# MASTER_CEAQL_PCB.net
KiCad netlist of a schematic drawn in EAGLE
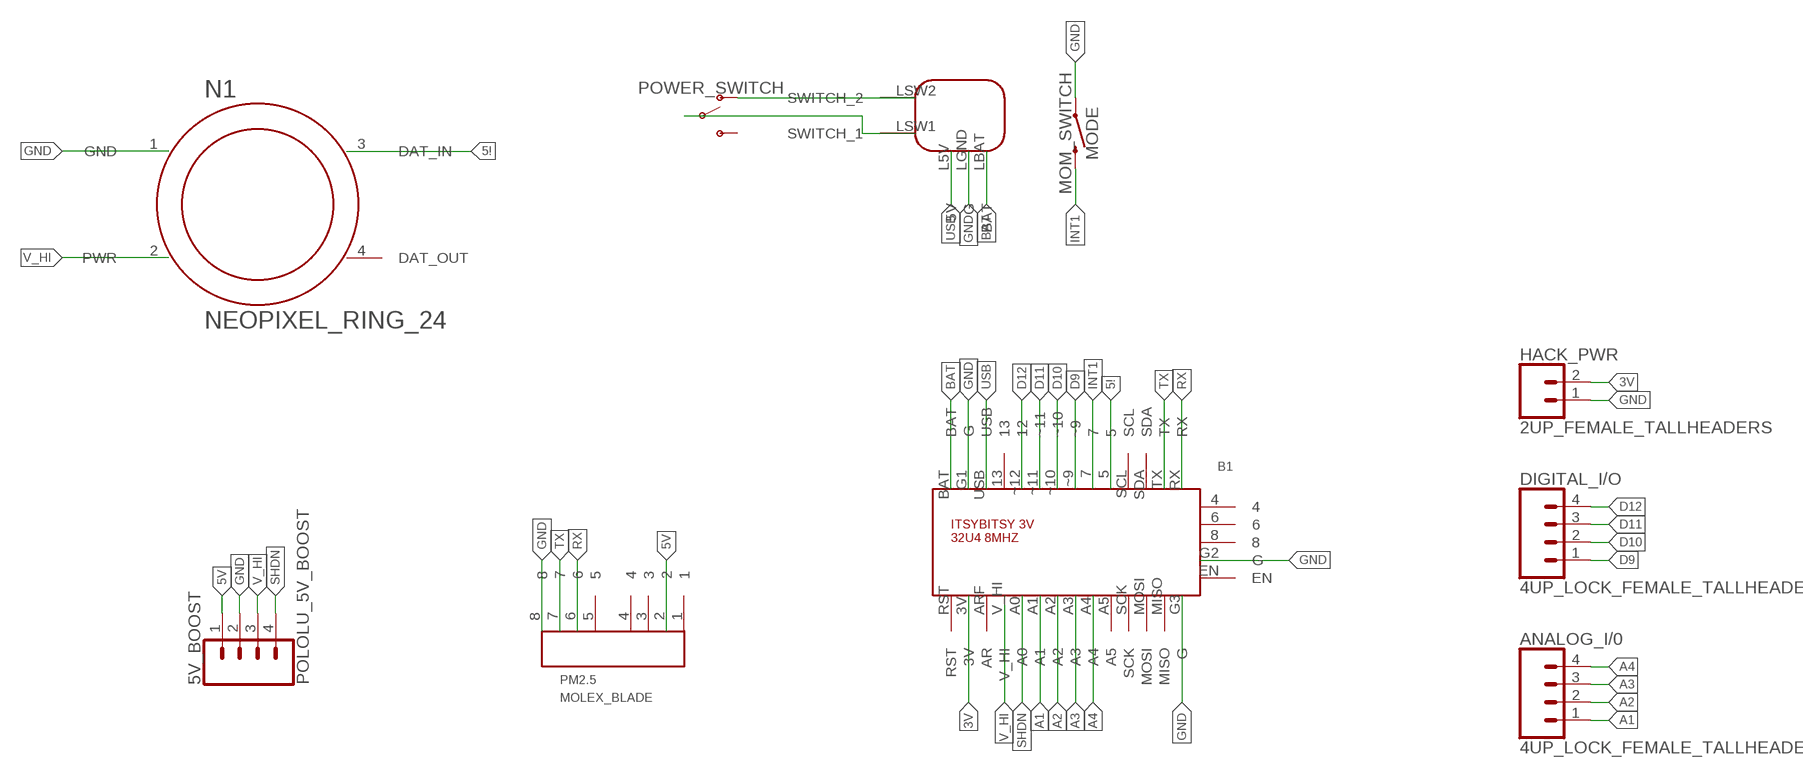
[diagram p0: schematic, sheet 1]

(export (version "E")
  (design (tool "Eeschema 10.0.6"))
  (components
    (comp (ref "5V_BOOST")
      (value "POLOLU_5V_BOOST")
      (footprint "eagle-import:POLOLU_5V_HEADERS")
      (libsource (lib "eagle-import") (part "POLOLU_5V_BOOST"))
    )
    (comp (ref "ANALOG_I/0")
      (value "4UP_LOCK_FEMALE_TALLHEADERS")
      (footprint "eagle-import:1X04_LOCK_TALL")
      (libsource (lib "eagle-import") (part "4UP_LOCK_FEMALE_TALLHEADERS"))
    )
    (comp (ref "B1")
      (value "ITSY_BITSY")
      (footprint "eagle-import:ITSY_BITSY")
      (libsource (lib "eagle-import") (part "ITSY_BITSY"))
    )
    (comp (ref "DIGITAL_I/O")
      (value "4UP_LOCK_FEMALE_TALLHEADERS")
      (footprint "eagle-import:1X04_LOCK_TALL")
      (libsource (lib "eagle-import") (part "4UP_LOCK_FEMALE_TALLHEADERS"))
    )
    (comp (ref "HACK_PWR")
      (value "2UP_FEMALE_TALLHEADERS")
      (footprint "eagle-import:1X02")
      (libsource (lib "eagle-import") (part "2UP_FEMALE_TALLHEADERS"))
    )
    (comp (ref "L1")
      (value "LIPOLY_CHARGER")
      (footprint "eagle-import:LIPOLY_CHARGER")
      (libsource (lib "eagle-import") (part "LIPOLY_CHARGER"))
    )
    (comp (ref "MODE")
      (value "MOM_SWITCH")
      (footprint "eagle-import:TACTILE_SWITCH_PTH_6.0MM")
      (libsource (lib "eagle-import") (part "MOM_SWITCH_B3F-1000"))
    )
    (comp (ref "N1")
      (value "NEOPIXEL_RING_24")
      (footprint "eagle-import:NEOPIXEL_RNG_24")
      (libsource (lib "eagle-import") (part "NEOPIXEL_RING_24"))
    )
    (comp (ref "PM2.5")
      (value "MOLEX_BLADE")
      (footprint "eagle-import:53047-08")
      (libsource (lib "eagle-import") (part "MOLEX_BLADE"))
    )
    (comp (ref "POWER_SWITCH")
      (value "SWITCH_SPDT_PINMOUNT")
      (footprint "eagle-import:SWITCH_SPDT_PTH_11.6X4.0MM_LOCK")
      (libsource (lib "eagle-import") (part "SWITCH_SPDT_PINMOUNT"))
    )
  )
  (nets
    (net (code "1") (name "/5~{}") (class "Default")
      (node (ref "B1") (pin "5") (pinfunction "5_5") (pintype "output"))
      (node (ref "N1") (pin "3") (pinfunction "DAT_IN_3") (pintype "bidirectional"))
    )
    (net (code "2") (name "3V") (class "Default")
      (node (ref "B1") (pin "3V") (pinfunction "3V_3V") (pintype "power_in"))
      (node (ref "HACK_PWR") (pin "2") (pinfunction "2_2") (pintype "passive"))
    )
    (net (code "3") (name "5V") (class "Default")
      (node (ref "5V_BOOST") (pin "1") (pinfunction "1_1") (pintype "passive"))
      (node (ref "PM2.5") (pin "2") (pinfunction "2_2") (pintype "bidirectional"))
    )
    (net (code "4") (name "A1") (class "Default")
      (node (ref "ANALOG_I/0") (pin "1") (pinfunction "1_1") (pintype "passive"))
      (node (ref "B1") (pin "A1") (pinfunction "A1_A1") (pintype "bidirectional"))
    )
    (net (code "5") (name "A2") (class "Default")
      (node (ref "ANALOG_I/0") (pin "2") (pinfunction "2_2") (pintype "passive"))
      (node (ref "B1") (pin "A2") (pinfunction "A2_A2") (pintype "bidirectional"))
    )
    (net (code "6") (name "A3") (class "Default")
      (node (ref "ANALOG_I/0") (pin "3") (pinfunction "3_3") (pintype "passive"))
      (node (ref "B1") (pin "A3") (pinfunction "A3_A3") (pintype "bidirectional"))
    )
    (net (code "7") (name "A4") (class "Default")
      (node (ref "ANALOG_I/0") (pin "4") (pinfunction "4_4") (pintype "passive"))
      (node (ref "B1") (pin "A4") (pinfunction "A4_A4") (pintype "bidirectional"))
    )
    (net (code "8") (name "BAT") (class "Default")
      (node (ref "B1") (pin "BAT") (pinfunction "BAT_BAT") (pintype "power_in"))
      (node (ref "L1") (pin "LBAT") (pinfunction "BAT_LBAT") (pintype "bidirectional"))
    )
    (net (code "9") (name "D9") (class "Default")
      (node (ref "B1") (pin "~9") (pinfunction "~{9}_~9") (pintype "bidirectional"))
      (node (ref "DIGITAL_I/O") (pin "1") (pinfunction "1_1") (pintype "passive"))
    )
    (net (code "10") (name "D10") (class "Default")
      (node (ref "B1") (pin "~10") (pinfunction "~{10}_~10") (pintype "bidirectional"))
      (node (ref "DIGITAL_I/O") (pin "2") (pinfunction "2_2") (pintype "passive"))
    )
    (net (code "11") (name "D11") (class "Default")
      (node (ref "B1") (pin "~11") (pinfunction "~{11}_~11") (pintype "bidirectional"))
      (node (ref "DIGITAL_I/O") (pin "3") (pinfunction "3_3") (pintype "passive"))
    )
    (net (code "12") (name "D12") (class "Default")
      (node (ref "B1") (pin "~12") (pinfunction "12_~12") (pintype "bidirectional"))
      (node (ref "DIGITAL_I/O") (pin "4") (pinfunction "4_4") (pintype "passive"))
    )
    (net (code "13") (name "GND") (class "Default")
      (node (ref "5V_BOOST") (pin "2") (pinfunction "2_2") (pintype "passive"))
      (node (ref "B1") (pin "G1") (pinfunction "G_G1") (pintype "power_in"))
      (node (ref "B1") (pin "G2") (pinfunction "G_G2") (pintype "power_in"))
      (node (ref "B1") (pin "G3") (pinfunction "G_G3") (pintype "power_in"))
      (node (ref "HACK_PWR") (pin "1") (pinfunction "1_1") (pintype "passive"))
      (node (ref "L1") (pin "LGND") (pinfunction "G_LGND") (pintype "bidirectional"))
      (node (ref "MODE") (pin "1") (pinfunction "1_1") (pintype "passive"))
      (node (ref "N1") (pin "1") (pinfunction "GND_1") (pintype "bidirectional"))
      (node (ref "PM2.5") (pin "8") (pinfunction "8_8") (pintype "bidirectional"))
    )
    (net (code "14") (name "INT1") (class "Default")
      (node (ref "B1") (pin "7") (pinfunction "7_7") (pintype "bidirectional"))
      (node (ref "MODE") (pin "2") (pinfunction "2_2") (pintype "passive"))
    )
    (net (code "15") (name "Net-(L1-SWITCH_1)") (class "Default")
      (node (ref "L1") (pin "LSW1") (pinfunction "SWITCH_1_LSW1") (pintype "bidirectional"))
      (node (ref "POWER_SWITCH") (pin "2") (pinfunction "P_2") (pintype "passive"))
    )
    (net (code "16") (name "Net-(L1-SWITCH_2)") (class "Default")
      (node (ref "L1") (pin "LSW2") (pinfunction "SWITCH_2_LSW2") (pintype "bidirectional"))
      (node (ref "POWER_SWITCH") (pin "1") (pinfunction "O_1") (pintype "passive"))
    )
    (net (code "17") (name "RX") (class "Default")
      (node (ref "B1") (pin "RX") (pinfunction "RX_RX") (pintype "bidirectional"))
      (node (ref "PM2.5") (pin "6") (pinfunction "6_6") (pintype "bidirectional"))
    )
    (net (code "18") (name "SHDN") (class "Default")
      (node (ref "5V_BOOST") (pin "4") (pinfunction "4_4") (pintype "passive"))
      (node (ref "B1") (pin "A0") (pinfunction "A0_A0") (pintype "bidirectional"))
    )
    (net (code "19") (name "TX") (class "Default")
      (node (ref "B1") (pin "TX") (pinfunction "TX_TX") (pintype "bidirectional"))
      (node (ref "PM2.5") (pin "7") (pinfunction "7_7") (pintype "bidirectional"))
    )
    (net (code "20") (name "USB") (class "Default")
      (node (ref "B1") (pin "USB") (pinfunction "USB_USB") (pintype "power_in"))
      (node (ref "L1") (pin "L5V") (pinfunction "5V_L5V") (pintype "bidirectional"))
    )
    (net (code "21") (name "V_HI") (class "Default")
      (node (ref "5V_BOOST") (pin "3") (pinfunction "3_3") (pintype "passive"))
      (node (ref "B1") (pin "V_HI") (pinfunction "V_HI_V_HI") (pintype "power_in"))
      (node (ref "N1") (pin "2") (pinfunction "PWR_2") (pintype "bidirectional"))
    )
    (net (code "22") (name "unconnected-(B1-AR-PadARF)") (class "Default")
      (node (ref "B1") (pin "ARF") (pinfunction "AR_ARF") (pintype "bidirectional"))
    )
    (net (code "23") (name "unconnected-(B1-Pad4)") (class "Default")
      (node (ref "B1") (pin "4") (pinfunction "4_4") (pintype "bidirectional"))
    )
    (net (code "24") (name "unconnected-(B1-Pad6)") (class "Default")
      (node (ref "B1") (pin "6") (pinfunction "6_6") (pintype "bidirectional"))
    )
    (net (code "25") (name "unconnected-(B1-Pad8)") (class "Default")
      (node (ref "B1") (pin "8") (pinfunction "8_8") (pintype "bidirectional"))
    )
    (net (code "26") (name "unconnected-(B1-Pad13)") (class "Default")
      (node (ref "B1") (pin "13") (pinfunction "13_13") (pintype "bidirectional"))
    )
    (net (code "27") (name "unconnected-(B1-PadA5)") (class "Default")
      (node (ref "B1") (pin "A5") (pinfunction "A5_A5") (pintype "bidirectional"))
    )
    (net (code "28") (name "unconnected-(B1-PadEN)") (class "Default")
      (node (ref "B1") (pin "EN") (pinfunction "EN_EN") (pintype "bidirectional"))
    )
    (net (code "29") (name "unconnected-(B1-PadMISO)") (class "Default")
      (node (ref "B1") (pin "MISO") (pinfunction "MISO_MISO") (pintype "bidirectional"))
    )
    (net (code "30") (name "unconnected-(B1-PadMOSI)") (class "Default")
      (node (ref "B1") (pin "MOSI") (pinfunction "MOSI_MOSI") (pintype "bidirectional"))
    )
    (net (code "31") (name "unconnected-(B1-PadRST)") (class "Default")
      (node (ref "B1") (pin "RST") (pinfunction "RST_RST") (pintype "bidirectional"))
    )
    (net (code "32") (name "unconnected-(B1-PadSCK)") (class "Default")
      (node (ref "B1") (pin "SCK") (pinfunction "SCK_SCK") (pintype "bidirectional"))
    )
    (net (code "33") (name "unconnected-(B1-PadSCL)") (class "Default")
      (node (ref "B1") (pin "SCL") (pinfunction "SCL_SCL") (pintype "bidirectional"))
    )
    (net (code "34") (name "unconnected-(B1-PadSDA)") (class "Default")
      (node (ref "B1") (pin "SDA") (pinfunction "SDA_SDA") (pintype "bidirectional"))
    )
    (net (code "35") (name "unconnected-(N1-DAT_OUT-Pad4)") (class "Default")
      (node (ref "N1") (pin "4") (pinfunction "DAT_OUT_4") (pintype "bidirectional"))
    )
    (net (code "36") (name "unconnected-(PM2.5-Pad1)") (class "Default")
      (node (ref "PM2.5") (pin "1") (pinfunction "1_1") (pintype "bidirectional"))
    )
    (net (code "37") (name "unconnected-(PM2.5-Pad3)") (class "Default")
      (node (ref "PM2.5") (pin "3") (pinfunction "3_3") (pintype "bidirectional"))
    )
    (net (code "38") (name "unconnected-(PM2.5-Pad4)") (class "Default")
      (node (ref "PM2.5") (pin "4") (pinfunction "4_4") (pintype "bidirectional"))
    )
    (net (code "39") (name "unconnected-(PM2.5-Pad5)") (class "Default")
      (node (ref "PM2.5") (pin "5") (pinfunction "5_5") (pintype "bidirectional"))
    )
    (net (code "40") (name "unconnected-(POWER_SWITCH-S-Pad3)") (class "Default")
      (node (ref "POWER_SWITCH") (pin "3") (pinfunction "S_3") (pintype "passive"))
    )
  )
)
